# probatio-rotary-16leds_3535.net
KiCad netlist of a schematic drawn in EAGLE
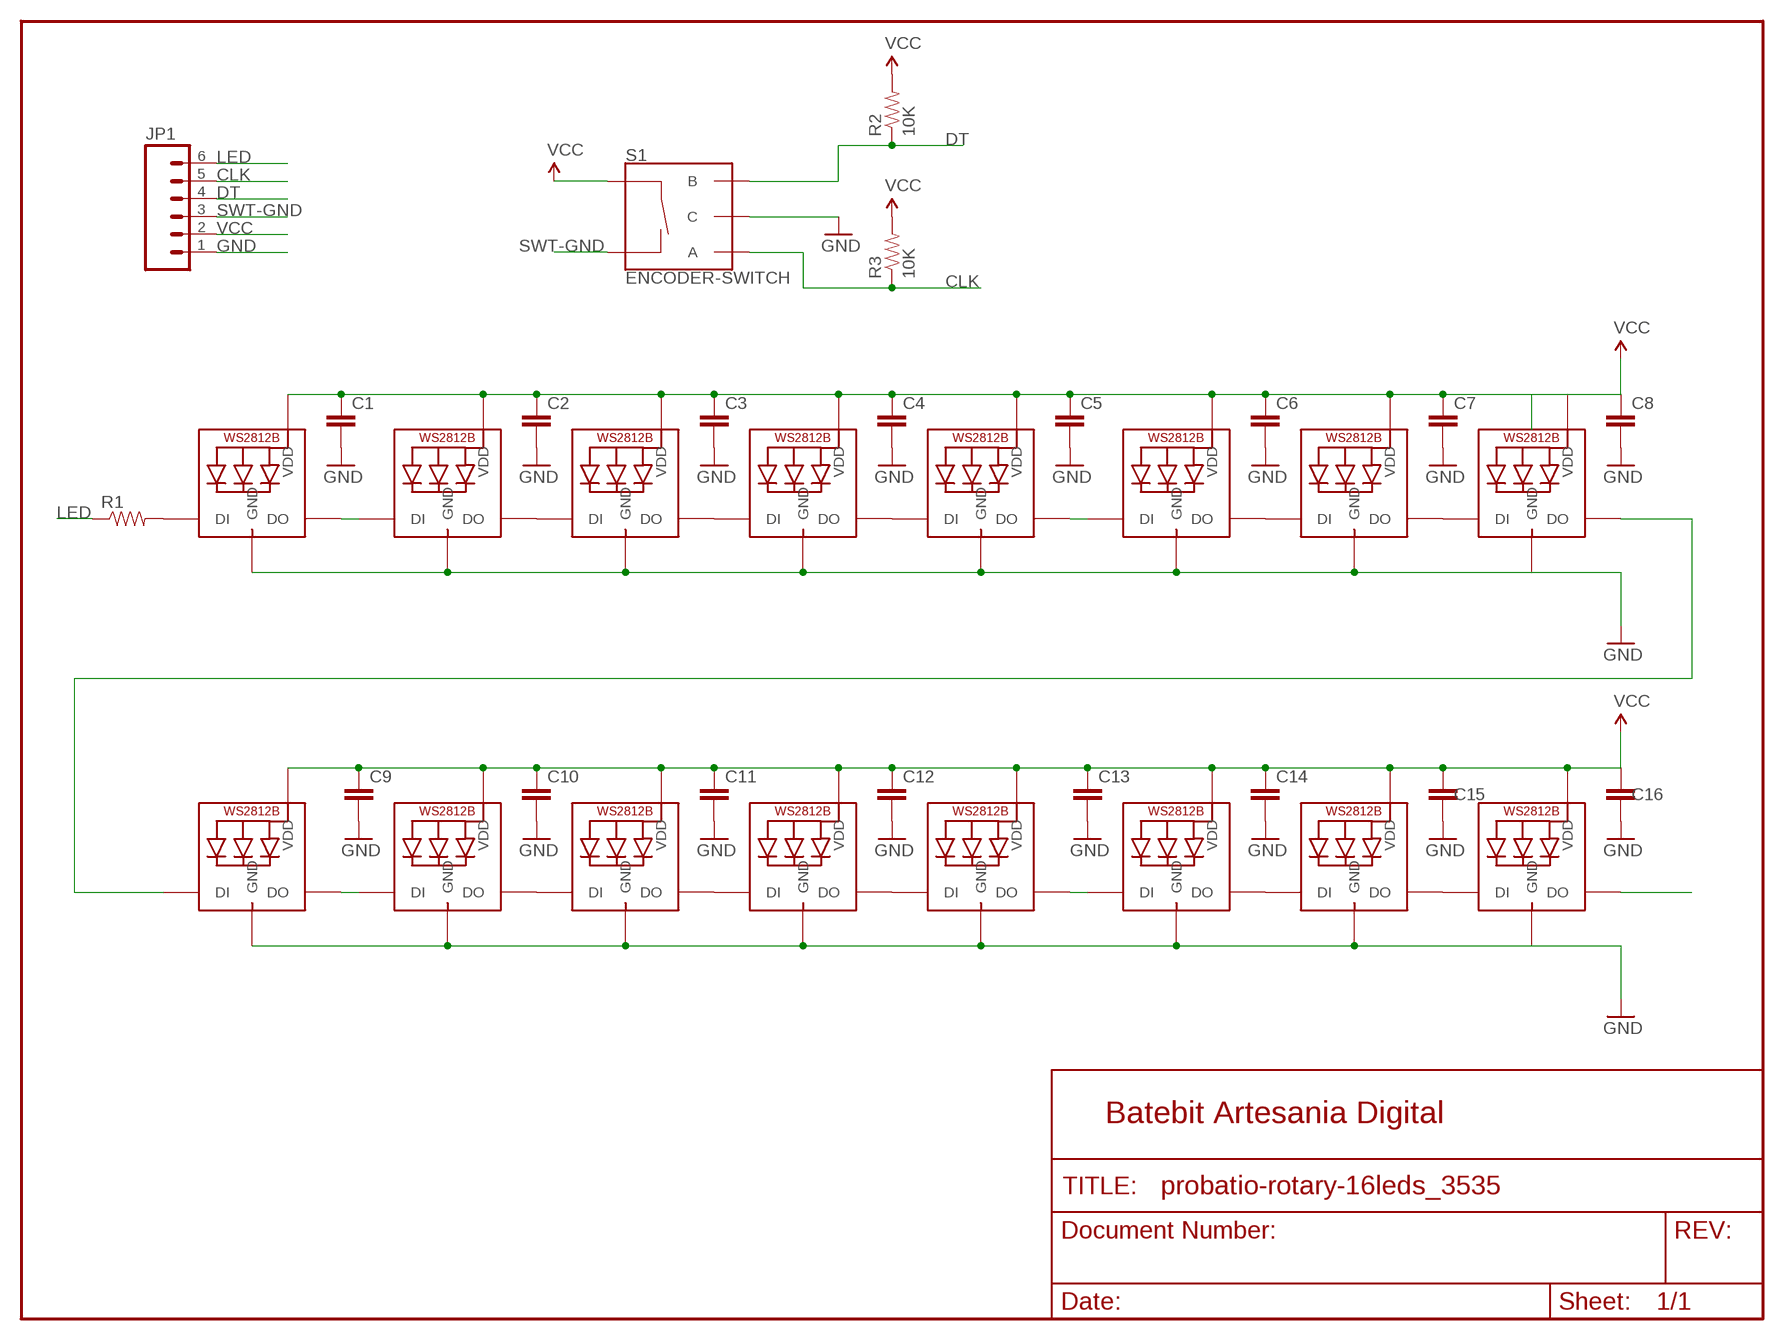
[diagram p0: schematic, sheet 1]

(export (version "E")
  (design (tool "Eeschema 10.0.6"))
  (components
    (comp (ref "C1")
      (value "CAP0805-CAP")
      (footprint "eagle-import:0805-CAP")
      (libsource (lib "eagle-import") (part "CAP0805-CAP"))
    )
    (comp (ref "C2")
      (value "CAP0805-CAP")
      (footprint "eagle-import:0805-CAP")
      (libsource (lib "eagle-import") (part "CAP0805-CAP"))
    )
    (comp (ref "C3")
      (value "CAP0805-CAP")
      (footprint "eagle-import:0805-CAP")
      (libsource (lib "eagle-import") (part "CAP0805-CAP"))
    )
    (comp (ref "C4")
      (value "CAP0805-CAP")
      (footprint "eagle-import:0805-CAP")
      (libsource (lib "eagle-import") (part "CAP0805-CAP"))
    )
    (comp (ref "C5")
      (value "CAP0805-CAP")
      (footprint "eagle-import:0805-CAP")
      (libsource (lib "eagle-import") (part "CAP0805-CAP"))
    )
    (comp (ref "C6")
      (value "CAP0805-CAP")
      (footprint "eagle-import:0805-CAP")
      (libsource (lib "eagle-import") (part "CAP0805-CAP"))
    )
    (comp (ref "C7")
      (value "CAP0805-CAP")
      (footprint "eagle-import:0805-CAP")
      (libsource (lib "eagle-import") (part "CAP0805-CAP"))
    )
    (comp (ref "C8")
      (value "CAP0805-CAP")
      (footprint "eagle-import:0805-CAP")
      (libsource (lib "eagle-import") (part "CAP0805-CAP"))
    )
    (comp (ref "C9")
      (value "CAP0805-CAP")
      (footprint "eagle-import:0805-CAP")
      (libsource (lib "eagle-import") (part "CAP0805-CAP"))
    )
    (comp (ref "C10")
      (value "CAP0805-CAP")
      (footprint "eagle-import:0805-CAP")
      (libsource (lib "eagle-import") (part "CAP0805-CAP"))
    )
    (comp (ref "C11")
      (value "CAP0805-CAP")
      (footprint "eagle-import:0805-CAP")
      (libsource (lib "eagle-import") (part "CAP0805-CAP"))
    )
    (comp (ref "C12")
      (value "CAP0805-CAP")
      (footprint "eagle-import:0805-CAP")
      (libsource (lib "eagle-import") (part "CAP0805-CAP"))
    )
    (comp (ref "C13")
      (value "CAP0805-CAP")
      (footprint "eagle-import:0805-CAP")
      (libsource (lib "eagle-import") (part "CAP0805-CAP"))
    )
    (comp (ref "C14")
      (value "CAP0805-CAP")
      (footprint "eagle-import:0805-CAP")
      (libsource (lib "eagle-import") (part "CAP0805-CAP"))
    )
    (comp (ref "C15")
      (value "CAP0805-CAP")
      (footprint "eagle-import:0805-CAP")
      (libsource (lib "eagle-import") (part "CAP0805-CAP"))
    )
    (comp (ref "C16")
      (value "CAP0805-CAP")
      (footprint "eagle-import:0805-CAP")
      (libsource (lib "eagle-import") (part "CAP0805-CAP"))
    )
    (comp (ref "JP1")
      (value "M06SILK_FEMALE_PTH")
      (footprint "eagle-import:1X06")
      (libsource (lib "eagle-import") (part "M06SILK_FEMALE_PTH"))
    )
    (comp (ref "LED1")
      (value "WS2812B3535")
      (footprint "eagle-import:LED3535")
      (libsource (lib "eagle-import") (part "WS2812B3535"))
    )
    (comp (ref "LED2")
      (value "WS2812B3535")
      (footprint "eagle-import:LED3535")
      (libsource (lib "eagle-import") (part "WS2812B3535"))
    )
    (comp (ref "LED3")
      (value "WS2812B3535")
      (footprint "eagle-import:LED3535")
      (libsource (lib "eagle-import") (part "WS2812B3535"))
    )
    (comp (ref "LED4")
      (value "WS2812B3535")
      (footprint "eagle-import:LED3535")
      (libsource (lib "eagle-import") (part "WS2812B3535"))
    )
    (comp (ref "LED5")
      (value "WS2812B3535")
      (footprint "eagle-import:LED3535")
      (libsource (lib "eagle-import") (part "WS2812B3535"))
    )
    (comp (ref "LED6")
      (value "WS2812B3535")
      (footprint "eagle-import:LED3535")
      (libsource (lib "eagle-import") (part "WS2812B3535"))
    )
    (comp (ref "LED7")
      (value "WS2812B3535")
      (footprint "eagle-import:LED3535")
      (libsource (lib "eagle-import") (part "WS2812B3535"))
    )
    (comp (ref "LED8")
      (value "WS2812B3535")
      (footprint "eagle-import:LED3535")
      (libsource (lib "eagle-import") (part "WS2812B3535"))
    )
    (comp (ref "LED9")
      (value "WS2812B3535")
      (footprint "eagle-import:LED3535")
      (libsource (lib "eagle-import") (part "WS2812B3535"))
    )
    (comp (ref "LED10")
      (value "WS2812B3535")
      (footprint "eagle-import:LED3535")
      (libsource (lib "eagle-import") (part "WS2812B3535"))
    )
    (comp (ref "LED11")
      (value "WS2812B3535")
      (footprint "eagle-import:LED3535")
      (libsource (lib "eagle-import") (part "WS2812B3535"))
    )
    (comp (ref "LED12")
      (value "WS2812B3535")
      (footprint "eagle-import:LED3535")
      (libsource (lib "eagle-import") (part "WS2812B3535"))
    )
    (comp (ref "LED13")
      (value "WS2812B3535")
      (footprint "eagle-import:LED3535")
      (libsource (lib "eagle-import") (part "WS2812B3535"))
    )
    (comp (ref "LED14")
      (value "WS2812B3535")
      (footprint "eagle-import:LED3535")
      (libsource (lib "eagle-import") (part "WS2812B3535"))
    )
    (comp (ref "LED15")
      (value "WS2812B3535")
      (footprint "eagle-import:LED3535")
      (libsource (lib "eagle-import") (part "WS2812B3535"))
    )
    (comp (ref "LED16")
      (value "WS2812B3535")
      (footprint "eagle-import:LED3535")
      (libsource (lib "eagle-import") (part "WS2812B3535"))
    )
    (comp (ref "R1")
      (value "RESISTOR0805-RES")
      (footprint "eagle-import:0805-RES")
      (libsource (lib "eagle-import") (part "RESISTOR0805-RES"))
    )
    (comp (ref "R2")
      (value "10K")
      (footprint "eagle-import:0805-RES")
      (libsource (lib "eagle-import") (part "RESISTOR0805-RES"))
    )
    (comp (ref "R3")
      (value "10K")
      (footprint "eagle-import:0805-RES")
      (libsource (lib "eagle-import") (part "RESISTOR0805-RES"))
    )
    (comp (ref "S1")
      (value "ENCODER-SWITCH")
      (footprint "eagle-import:ROTARY_ENC_PLAIN")
      (libsource (lib "eagle-import") (part "ENCODER-SWITCH"))
    )
  )
  (nets
    (net (code "1") (name "/CLK") (class "Default")
      (node (ref "JP1") (pin "5") (pinfunction "5_5") (pintype "passive"))
      (node (ref "R3") (pin "1") (pinfunction "1_1") (pintype "passive"))
      (node (ref "S1") (pin "A") (pinfunction "A_A") (pintype "bidirectional"))
    )
    (net (code "2") (name "/DT") (class "Default")
      (node (ref "JP1") (pin "4") (pinfunction "4_4") (pintype "passive"))
      (node (ref "R2") (pin "1") (pinfunction "1_1") (pintype "passive"))
      (node (ref "S1") (pin "B") (pinfunction "B_B") (pintype "bidirectional"))
    )
    (net (code "3") (name "/LED") (class "Default")
      (node (ref "JP1") (pin "6") (pinfunction "6_6") (pintype "passive"))
      (node (ref "R1") (pin "1") (pinfunction "1_1") (pintype "passive"))
    )
    (net (code "4") (name "/SWT-GND") (class "Default")
      (node (ref "JP1") (pin "3") (pinfunction "3_3") (pintype "passive"))
      (node (ref "S1") (pin "SW-") (pinfunction "SW-_SW-") (pintype "bidirectional"))
    )
    (net (code "5") (name "GND") (class "Default")
      (node (ref "C1") (pin "2") (pinfunction "2_2") (pintype "passive"))
      (node (ref "C10") (pin "2") (pinfunction "2_2") (pintype "passive"))
      (node (ref "C11") (pin "2") (pinfunction "2_2") (pintype "passive"))
      (node (ref "C12") (pin "2") (pinfunction "2_2") (pintype "passive"))
      (node (ref "C13") (pin "2") (pinfunction "2_2") (pintype "passive"))
      (node (ref "C14") (pin "2") (pinfunction "2_2") (pintype "passive"))
      (node (ref "C15") (pin "2") (pinfunction "2_2") (pintype "passive"))
      (node (ref "C16") (pin "2") (pinfunction "2_2") (pintype "passive"))
      (node (ref "C2") (pin "2") (pinfunction "2_2") (pintype "passive"))
      (node (ref "C3") (pin "2") (pinfunction "2_2") (pintype "passive"))
      (node (ref "C4") (pin "2") (pinfunction "2_2") (pintype "passive"))
      (node (ref "C5") (pin "2") (pinfunction "2_2") (pintype "passive"))
      (node (ref "C6") (pin "2") (pinfunction "2_2") (pintype "passive"))
      (node (ref "C7") (pin "2") (pinfunction "2_2") (pintype "passive"))
      (node (ref "C8") (pin "2") (pinfunction "2_2") (pintype "passive"))
      (node (ref "C9") (pin "2") (pinfunction "2_2") (pintype "passive"))
      (node (ref "JP1") (pin "1") (pinfunction "1_1") (pintype "passive"))
      (node (ref "LED1") (pin "4") (pinfunction "GND_4") (pintype "power_in"))
      (node (ref "LED10") (pin "4") (pinfunction "GND_4") (pintype "power_in"))
      (node (ref "LED11") (pin "4") (pinfunction "GND_4") (pintype "power_in"))
      (node (ref "LED12") (pin "4") (pinfunction "GND_4") (pintype "power_in"))
      (node (ref "LED13") (pin "4") (pinfunction "GND_4") (pintype "power_in"))
      (node (ref "LED14") (pin "4") (pinfunction "GND_4") (pintype "power_in"))
      (node (ref "LED15") (pin "4") (pinfunction "GND_4") (pintype "power_in"))
      (node (ref "LED16") (pin "4") (pinfunction "GND_4") (pintype "power_in"))
      (node (ref "LED2") (pin "4") (pinfunction "GND_4") (pintype "power_in"))
      (node (ref "LED3") (pin "4") (pinfunction "GND_4") (pintype "power_in"))
      (node (ref "LED4") (pin "4") (pinfunction "GND_4") (pintype "power_in"))
      (node (ref "LED5") (pin "4") (pinfunction "GND_4") (pintype "power_in"))
      (node (ref "LED6") (pin "4") (pinfunction "GND_4") (pintype "power_in"))
      (node (ref "LED7") (pin "4") (pinfunction "GND_4") (pintype "power_in"))
      (node (ref "LED8") (pin "4") (pinfunction "GND_4") (pintype "power_in"))
      (node (ref "LED9") (pin "4") (pinfunction "GND_4") (pintype "power_in"))
      (node (ref "S1") (pin "C") (pinfunction "C_C") (pintype "bidirectional"))
    )
    (net (code "6") (name "Net-(LED1-DI)") (class "Default")
      (node (ref "LED1") (pin "1") (pinfunction "DI_1") (pintype "input"))
      (node (ref "R1") (pin "2") (pinfunction "2_2") (pintype "passive"))
    )
    (net (code "7") (name "Net-(LED1-DO)") (class "Default")
      (node (ref "LED1") (pin "3") (pinfunction "DO_3") (pintype "output"))
      (node (ref "LED2") (pin "1") (pinfunction "DI_1") (pintype "input"))
    )
    (net (code "8") (name "Net-(LED2-DO)") (class "Default")
      (node (ref "LED2") (pin "3") (pinfunction "DO_3") (pintype "output"))
      (node (ref "LED3") (pin "1") (pinfunction "DI_1") (pintype "input"))
    )
    (net (code "9") (name "Net-(LED3-DO)") (class "Default")
      (node (ref "LED3") (pin "3") (pinfunction "DO_3") (pintype "output"))
      (node (ref "LED4") (pin "1") (pinfunction "DI_1") (pintype "input"))
    )
    (net (code "10") (name "Net-(LED4-DO)") (class "Default")
      (node (ref "LED4") (pin "3") (pinfunction "DO_3") (pintype "output"))
      (node (ref "LED5") (pin "1") (pinfunction "DI_1") (pintype "input"))
    )
    (net (code "11") (name "Net-(LED5-DO)") (class "Default")
      (node (ref "LED5") (pin "3") (pinfunction "DO_3") (pintype "output"))
      (node (ref "LED6") (pin "1") (pinfunction "DI_1") (pintype "input"))
    )
    (net (code "12") (name "Net-(LED6-DO)") (class "Default")
      (node (ref "LED6") (pin "3") (pinfunction "DO_3") (pintype "output"))
      (node (ref "LED7") (pin "1") (pinfunction "DI_1") (pintype "input"))
    )
    (net (code "13") (name "Net-(LED7-DO)") (class "Default")
      (node (ref "LED7") (pin "3") (pinfunction "DO_3") (pintype "output"))
      (node (ref "LED8") (pin "1") (pinfunction "DI_1") (pintype "input"))
    )
    (net (code "14") (name "Net-(LED8-DO)") (class "Default")
      (node (ref "LED8") (pin "3") (pinfunction "DO_3") (pintype "output"))
      (node (ref "LED9") (pin "1") (pinfunction "DI_1") (pintype "input"))
    )
    (net (code "15") (name "Net-(LED10-DI)") (class "Default")
      (node (ref "LED10") (pin "1") (pinfunction "DI_1") (pintype "input"))
      (node (ref "LED9") (pin "3") (pinfunction "DO_3") (pintype "output"))
    )
    (net (code "16") (name "Net-(LED10-DO)") (class "Default")
      (node (ref "LED10") (pin "3") (pinfunction "DO_3") (pintype "output"))
      (node (ref "LED11") (pin "1") (pinfunction "DI_1") (pintype "input"))
    )
    (net (code "17") (name "Net-(LED11-DO)") (class "Default")
      (node (ref "LED11") (pin "3") (pinfunction "DO_3") (pintype "output"))
      (node (ref "LED12") (pin "1") (pinfunction "DI_1") (pintype "input"))
    )
    (net (code "18") (name "Net-(LED12-DO)") (class "Default")
      (node (ref "LED12") (pin "3") (pinfunction "DO_3") (pintype "output"))
      (node (ref "LED13") (pin "1") (pinfunction "DI_1") (pintype "input"))
    )
    (net (code "19") (name "Net-(LED13-DO)") (class "Default")
      (node (ref "LED13") (pin "3") (pinfunction "DO_3") (pintype "output"))
      (node (ref "LED14") (pin "1") (pinfunction "DI_1") (pintype "input"))
    )
    (net (code "20") (name "Net-(LED14-DO)") (class "Default")
      (node (ref "LED14") (pin "3") (pinfunction "DO_3") (pintype "output"))
      (node (ref "LED15") (pin "1") (pinfunction "DI_1") (pintype "input"))
    )
    (net (code "21") (name "Net-(LED15-DO)") (class "Default")
      (node (ref "LED15") (pin "3") (pinfunction "DO_3") (pintype "output"))
      (node (ref "LED16") (pin "1") (pinfunction "DI_1") (pintype "input"))
    )
    (net (code "22") (name "VCC") (class "Default")
      (node (ref "C1") (pin "1") (pinfunction "1_1") (pintype "passive"))
      (node (ref "C10") (pin "1") (pinfunction "1_1") (pintype "passive"))
      (node (ref "C11") (pin "1") (pinfunction "1_1") (pintype "passive"))
      (node (ref "C12") (pin "1") (pinfunction "1_1") (pintype "passive"))
      (node (ref "C13") (pin "1") (pinfunction "1_1") (pintype "passive"))
      (node (ref "C14") (pin "1") (pinfunction "1_1") (pintype "passive"))
      (node (ref "C15") (pin "1") (pinfunction "1_1") (pintype "passive"))
      (node (ref "C16") (pin "1") (pinfunction "1_1") (pintype "passive"))
      (node (ref "C2") (pin "1") (pinfunction "1_1") (pintype "passive"))
      (node (ref "C3") (pin "1") (pinfunction "1_1") (pintype "passive"))
      (node (ref "C4") (pin "1") (pinfunction "1_1") (pintype "passive"))
      (node (ref "C5") (pin "1") (pinfunction "1_1") (pintype "passive"))
      (node (ref "C6") (pin "1") (pinfunction "1_1") (pintype "passive"))
      (node (ref "C7") (pin "1") (pinfunction "1_1") (pintype "passive"))
      (node (ref "C8") (pin "1") (pinfunction "1_1") (pintype "passive"))
      (node (ref "C9") (pin "1") (pinfunction "1_1") (pintype "passive"))
      (node (ref "JP1") (pin "2") (pinfunction "2_2") (pintype "passive"))
      (node (ref "LED1") (pin "2") (pinfunction "VDD_2") (pintype "power_in"))
      (node (ref "LED10") (pin "2") (pinfunction "VDD_2") (pintype "power_in"))
      (node (ref "LED11") (pin "2") (pinfunction "VDD_2") (pintype "power_in"))
      (node (ref "LED12") (pin "2") (pinfunction "VDD_2") (pintype "power_in"))
      (node (ref "LED13") (pin "2") (pinfunction "VDD_2") (pintype "power_in"))
      (node (ref "LED14") (pin "2") (pinfunction "VDD_2") (pintype "power_in"))
      (node (ref "LED15") (pin "2") (pinfunction "VDD_2") (pintype "power_in"))
      (node (ref "LED16") (pin "2") (pinfunction "VDD_2") (pintype "power_in"))
      (node (ref "LED2") (pin "2") (pinfunction "VDD_2") (pintype "power_in"))
      (node (ref "LED3") (pin "2") (pinfunction "VDD_2") (pintype "power_in"))
      (node (ref "LED4") (pin "2") (pinfunction "VDD_2") (pintype "power_in"))
      (node (ref "LED5") (pin "2") (pinfunction "VDD_2") (pintype "power_in"))
      (node (ref "LED6") (pin "2") (pinfunction "VDD_2") (pintype "power_in"))
      (node (ref "LED7") (pin "2") (pinfunction "VDD_2") (pintype "power_in"))
      (node (ref "LED8") (pin "2") (pinfunction "VDD_2") (pintype "power_in"))
      (node (ref "LED9") (pin "2") (pinfunction "VDD_2") (pintype "power_in"))
      (node (ref "R2") (pin "2") (pinfunction "2_2") (pintype "passive"))
      (node (ref "R3") (pin "2") (pinfunction "2_2") (pintype "passive"))
      (node (ref "S1") (pin "SW+") (pinfunction "SW+_SW+") (pintype "bidirectional"))
    )
    (net (code "23") (name "unconnected-(LED16-DO-Pad3)") (class "Default")
      (node (ref "LED16") (pin "3") (pinfunction "DO_3") (pintype "output"))
    )
  )
)
